# design.net
KiCad netlist of a schematic drawn in Altium Designer
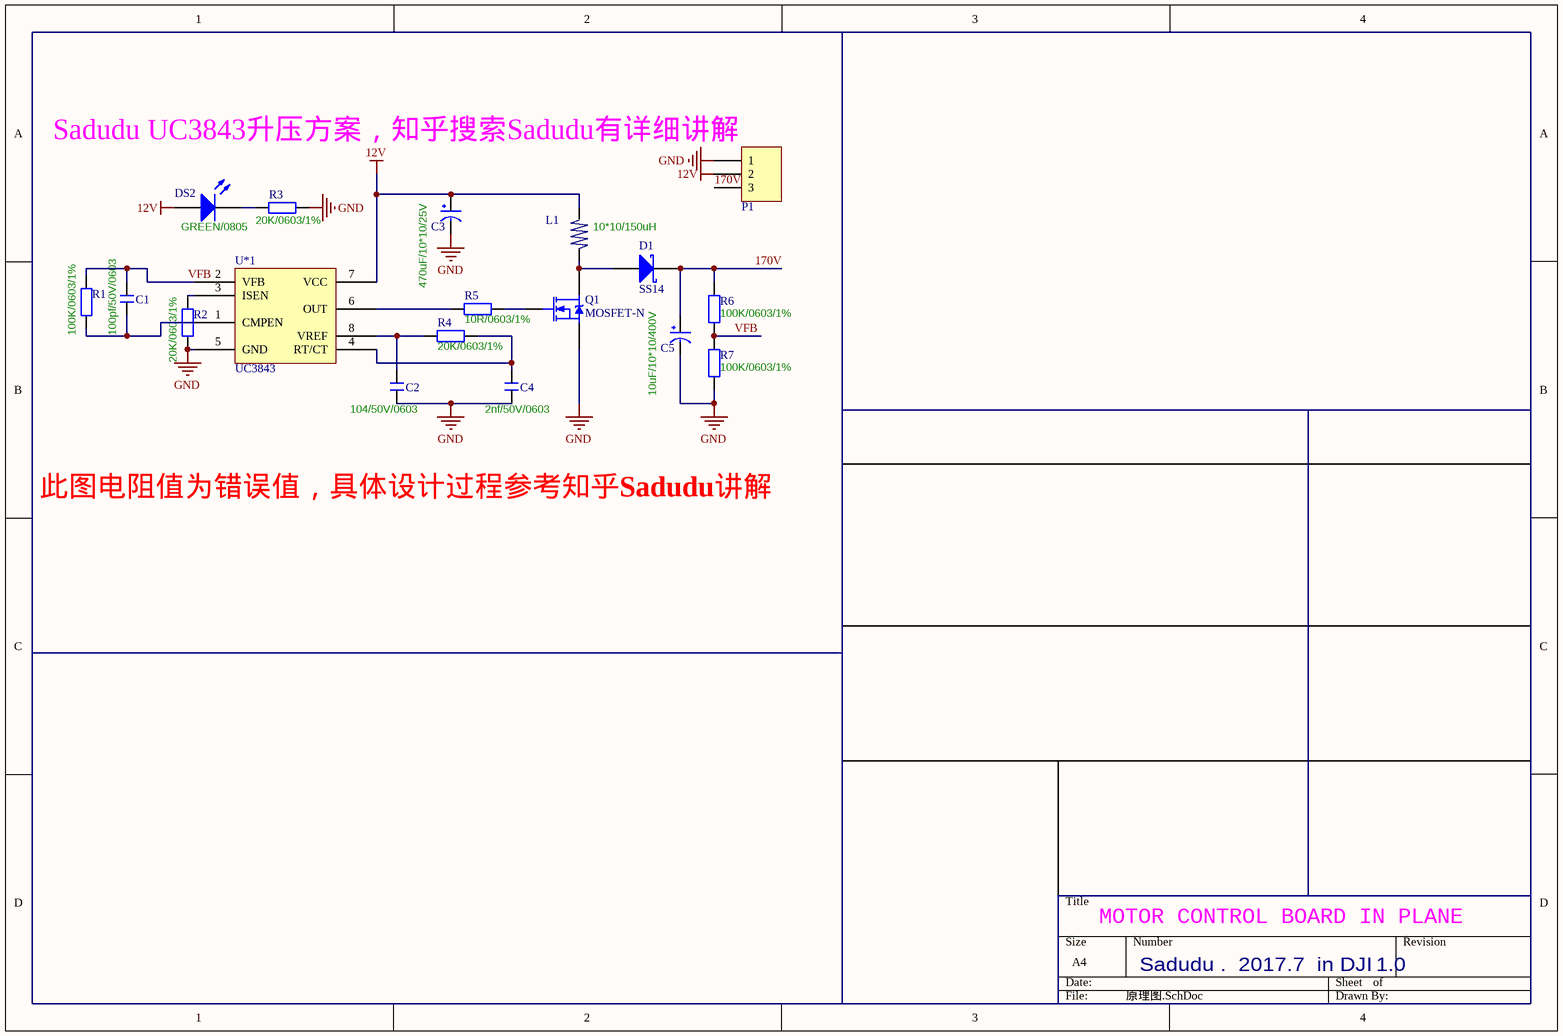
[diagram p0: 原理图.SchDoc]

(export (version "E")
  (design (tool "Eeschema 10.0.6"))
  (components
    (comp (ref "C1") (value "100pf/50V/0603") (footprint "C-RAD-0603") (libsource (lib "dudu") (part "C_1")))
    (comp (ref "C2") (value "104/50V/0603") (footprint "C-RAD-0603") (libsource (lib "dudu") (part "C_1")))
    (comp (ref "C3") (value "470uF/10*10/25V") (footprint "C-RAD-0805") (libsource (lib "dudu") (part "CAP")))
    (comp (ref "C4") (value "2nf/50V/0603") (footprint "C-RAD-0603") (libsource (lib "dudu") (part "C_1")))
    (comp (ref "C5") (value "10uF/10*10/400V") (footprint "5032") (libsource (lib "dudu") (part "CAP")))
    (comp (ref "D1")
      (value "D-Schottky")
      (footprint "DIODE-SMA")
      (description "肖特基二极管")
      (fields (field (name "TYPE") "SS14") (field (name "PUBLISHER") "Altium Limited"))
      (libsource (lib "fszhang") (part "D-Schottky"))
    )
    (comp (ref "DS2")
      (value "GREEN/0805")
      (footprint "SMDLED")
      (description "Typical RED, GREEN, YELLOW, AMBER GaAs LED")
      (fields (field (name "PUBLISHER") "Altium Limited"))
      (libsource (lib "dudu") (part "LED2"))
    )
    (comp (ref "L1") (value "10*10/150uH") (footprint "L1010") (libsource (lib "dudu") (part "L")))
    (comp (ref "P1")
      (value "Header 3")
      (footprint "HEADER-3")
      (description "接插件")
      (fields (field (name "PUBLISHER") "Altium Limited"))
      (libsource (lib "fszhang") (part "Header 3"))
    )
    (comp (ref "Q1")
      (value "MOSFET-N")
      (footprint "D-PAK")
      (description "N-Channel MOSFET")
      (fields (field (name "PUBLISHER") "Altium Limited"))
      (libsource (lib "fszhang") (part "MOSFET-N"))
    )
    (comp (ref "R1")
      (value "100K/0603/1%")
      (footprint "0603-1")
      (description "贴片电阻")
      (fields (field (name "Comment") "Res1") (field (name "PUBLISHER") "Altium Limited"))
      (libsource (lib "") (part "Res1_3"))
    )
    (comp (ref "R2")
      (value "20K/0603/1%")
      (footprint "0603-1")
      (description "贴片电阻")
      (fields (field (name "Comment") "Res1") (field (name "PUBLISHER") "Altium Limited"))
      (libsource (lib "") (part "Res1_1"))
    )
    (comp (ref "R3")
      (value "20K/0603/1%")
      (footprint "0603-1")
      (description "贴片电阻")
      (fields (field (name "Comment") "Res1") (field (name "PUBLISHER") "Altium Limited"))
      (libsource (lib "") (part "Res1_2"))
    )
    (comp (ref "R4")
      (value "20K/0603/1%")
      (footprint "0603-1")
      (description "贴片电阻")
      (fields (field (name "Comment") "Res1") (field (name "PUBLISHER") "Altium Limited"))
      (libsource (lib "Fszhang") (part "Res1"))
    )
    (comp (ref "R5")
      (value "10R/0603/1%")
      (footprint "0603-1")
      (description "贴片电阻")
      (fields (field (name "Comment") "Res1") (field (name "PUBLISHER") "Altium Limited"))
      (libsource (lib "Fszhang") (part "Res1"))
    )
    (comp (ref "R6")
      (value "100K/0603/1%")
      (footprint "0603-1")
      (description "贴片电阻")
      (fields (field (name "Comment") "Res1") (field (name "PUBLISHER") "Altium Limited"))
      (libsource (lib "") (part "Res1_1"))
    )
    (comp (ref "R7")
      (value "100K/0603/1%")
      (footprint "0603-1")
      (description "贴片电阻")
      (fields (field (name "Comment") "Res1") (field (name "PUBLISHER") "Altium Limited"))
      (libsource (lib "") (part "Res1_1"))
    )
    (comp (ref "U*1") (value "UC3843") (footprint "SOP-8") (libsource (lib "dudu") (part "UC3843")))
  )
  (nets
    (net (code "1") (name "/170V") (class "Default")
      (node (ref "C5") (pin "1") (pinfunction "VCC_1") (pintype "passive"))
      (node (ref "D1") (pin "2") (pinfunction "K_2") (pintype "passive"))
      (node (ref "P1") (pin "3") (pinfunction "3_3") (pintype "passive"))
      (node (ref "R6") (pin "2") (pinfunction "2_2") (pintype "passive"))
    )
    (net (code "2") (name "/VFB") (class "Default")
      (node (ref "C1") (pin "1") (pintype "passive"))
      (node (ref "R1") (pin "1") (pinfunction "1_1") (pintype "passive"))
      (node (ref "R6") (pin "1") (pinfunction "1_1") (pintype "passive"))
      (node (ref "R7") (pin "2") (pinfunction "2_2") (pintype "passive"))
      (node (ref "U*1") (pin "2") (pinfunction "VFB_2") (pintype "passive"))
    )
    (net (code "3") (name "12V") (class "Default")
      (node (ref "C3") (pin "1") (pinfunction "VCC_1") (pintype "passive"))
      (node (ref "DS2") (pin "1") (pinfunction "A_1") (pintype "passive"))
      (node (ref "L1") (pin "1") (pintype "passive"))
      (node (ref "P1") (pin "2") (pinfunction "2_2") (pintype "passive"))
      (node (ref "U*1") (pin "7") (pinfunction "VCC_7") (pintype "passive"))
    )
    (net (code "4") (name "GND") (class "Default")
      (node (ref "C2") (pin "1") (pintype "passive"))
      (node (ref "C3") (pin "2") (pinfunction "GND_2") (pintype "passive"))
      (node (ref "C4") (pin "1") (pintype "passive"))
      (node (ref "C5") (pin "2") (pinfunction "GND_2") (pintype "passive"))
      (node (ref "P1") (pin "1") (pinfunction "1_1") (pintype "passive"))
      (node (ref "Q1") (pin "S") (pinfunction "S_S") (pintype "passive"))
      (node (ref "R2") (pin "1") (pinfunction "1_1") (pintype "passive"))
      (node (ref "R3") (pin "1") (pinfunction "1_1") (pintype "passive"))
      (node (ref "R7") (pin "1") (pinfunction "1_1") (pintype "passive"))
      (node (ref "U*1") (pin "5") (pinfunction "GND_5") (pintype "passive"))
    )
    (net (code "5") (name "Net-(D1-A)") (class "Default")
      (node (ref "D1") (pin "1") (pinfunction "A_1") (pintype "passive"))
      (node (ref "L1") (pin "2") (pintype "passive"))
      (node (ref "Q1") (pin "D") (pinfunction "D_D") (pintype "passive"))
    )
    (net (code "6") (name "Net-(DS2-K)") (class "Default")
      (node (ref "DS2") (pin "2") (pinfunction "K_2") (pintype "passive"))
      (node (ref "R3") (pin "2") (pinfunction "2_2") (pintype "passive"))
    )
    (net (code "7") (name "Net-(Q1-PadG)") (class "Default")
      (node (ref "Q1") (pin "G") (pinfunction "G_G") (pintype "passive"))
      (node (ref "R5") (pin "2") (pinfunction "2_2") (pintype "passive"))
    )
    (net (code "8") (name "Net-(U*1-CMPEN)") (class "Default")
      (node (ref "C1") (pin "2") (pintype "passive"))
      (node (ref "R1") (pin "2") (pinfunction "2_2") (pintype "passive"))
      (node (ref "U*1") (pin "1") (pinfunction "CMPEN_1") (pintype "passive"))
    )
    (net (code "9") (name "Net-(U*1-ISEN)") (class "Default")
      (node (ref "R2") (pin "2") (pinfunction "2_2") (pintype "passive"))
      (node (ref "U*1") (pin "3") (pinfunction "ISEN_3") (pintype "passive"))
    )
    (net (code "10") (name "Net-(U*1-OUT)") (class "Default")
      (node (ref "R5") (pin "1") (pinfunction "1_1") (pintype "passive"))
      (node (ref "U*1") (pin "6") (pinfunction "OUT_6") (pintype "passive"))
    )
    (net (code "11") (name "Net-(U*1-RT{slash}CT)") (class "Default")
      (node (ref "C4") (pin "2") (pintype "passive"))
      (node (ref "R4") (pin "2") (pinfunction "2_2") (pintype "passive"))
      (node (ref "U*1") (pin "4") (pinfunction "RT/CT_4") (pintype "passive"))
    )
    (net (code "12") (name "Net-(U*1-VREF)") (class "Default")
      (node (ref "C2") (pin "2") (pintype "passive"))
      (node (ref "R4") (pin "1") (pinfunction "1_1") (pintype "passive"))
      (node (ref "U*1") (pin "8") (pinfunction "VREF_8") (pintype "passive"))
    )
  )
)
